# NG3ControllerBoard.net
KiCad netlist of a schematic drawn in EAGLE
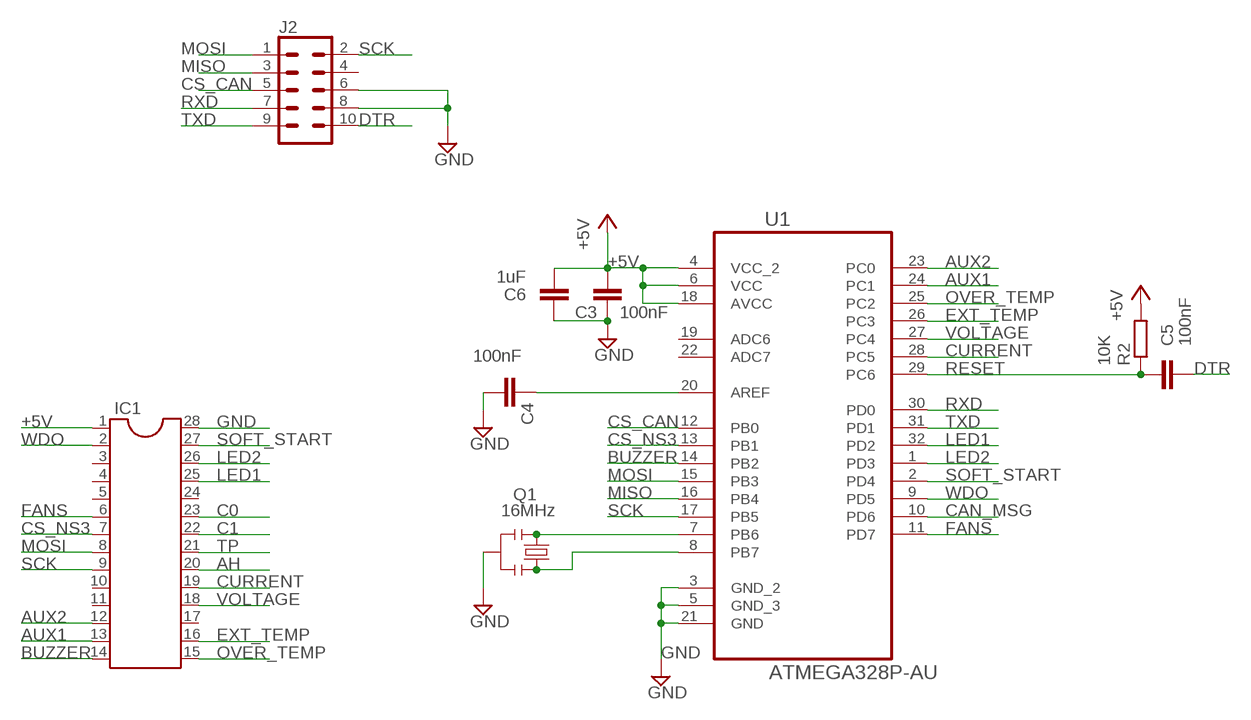
[diagram p0: schematic, sheet 1]

(export (version "E")
  (design (tool "Eeschema 10.0.6"))
  (components
    (comp (ref "C3")
      (value "100nF")
      (footprint "eagle-import:C0603")
      (libsource (lib "eagle-import") (part "C-EUC0603"))
    )
    (comp (ref "C4")
      (value "100nF")
      (footprint "eagle-import:C0603")
      (libsource (lib "eagle-import") (part "C-EUC0603"))
    )
    (comp (ref "C5")
      (value "100nF")
      (footprint "eagle-import:C0603")
      (libsource (lib "eagle-import") (part "C-EUC0603"))
    )
    (comp (ref "C6")
      (value "1uF")
      (footprint "eagle-import:C0805")
      (libsource (lib "eagle-import") (part "C-EUC0805"))
    )
    (comp (ref "IC1")
      (value "DIL28")
      (footprint "eagle-import:DIL28-6")
      (libsource (lib "eagle-import") (part "DIL28"))
    )
    (comp (ref "J2")
      (value "CONN_05X2PTH")
      (footprint "eagle-import:2X5")
      (libsource (lib "eagle-import") (part "CONN_05X2PTH"))
    )
    (comp (ref "Q1")
      (value "16MHz")
      (footprint "eagle-import:RESONATOR-SMD")
      (libsource (lib "eagle-import") (part "RESONATORSMD"))
    )
    (comp (ref "R2")
      (value "10K")
      (footprint "eagle-import:R0603")
      (libsource (lib "eagle-import") (part "R-EU_R0603"))
    )
    (comp (ref "U1")
      (value "ATMEGA328P-AU")
      (footprint "eagle-import:QFP80P900X900X120-32N")
      (libsource (lib "eagle-import") (part "ATMEGA328P-AU"))
    )
  )
  (nets
    (net (code "1") (name "+5V") (class "Default")
      (node (ref "C3") (pin "2") (pinfunction "2_2") (pintype "passive"))
      (node (ref "C6") (pin "2") (pinfunction "2_2") (pintype "passive"))
      (node (ref "IC1") (pin "1") (pinfunction "1_1") (pintype "passive"))
      (node (ref "R2") (pin "2") (pinfunction "2_2") (pintype "passive"))
      (node (ref "U1") (pin "18") (pinfunction "AVCC_18") (pintype "power_in"))
      (node (ref "U1") (pin "4") (pinfunction "VCC_2_4") (pintype "power_in"))
      (node (ref "U1") (pin "6") (pinfunction "VCC_6") (pintype "power_in"))
    )
    (net (code "2") (name "/AH") (class "Default")
      (node (ref "IC1") (pin "20") (pinfunction "20_20") (pintype "passive"))
    )
    (net (code "3") (name "/AUX1") (class "Default")
      (node (ref "IC1") (pin "13") (pinfunction "13_13") (pintype "passive"))
      (node (ref "U1") (pin "24") (pinfunction "PC1_24") (pintype "bidirectional"))
    )
    (net (code "4") (name "/AUX2") (class "Default")
      (node (ref "IC1") (pin "12") (pinfunction "12_12") (pintype "passive"))
      (node (ref "U1") (pin "23") (pinfunction "PC0_23") (pintype "bidirectional"))
    )
    (net (code "5") (name "/BUZZER") (class "Default")
      (node (ref "IC1") (pin "14") (pinfunction "14_14") (pintype "passive"))
      (node (ref "U1") (pin "14") (pinfunction "PB2_14") (pintype "bidirectional"))
    )
    (net (code "6") (name "/C0") (class "Default")
      (node (ref "IC1") (pin "23") (pinfunction "23_23") (pintype "passive"))
    )
    (net (code "7") (name "/C1") (class "Default")
      (node (ref "IC1") (pin "22") (pinfunction "22_22") (pintype "passive"))
    )
    (net (code "8") (name "/CAN_MSG") (class "Default")
      (node (ref "U1") (pin "10") (pinfunction "PD6_10") (pintype "bidirectional"))
    )
    (net (code "9") (name "/CS_CAN") (class "Default")
      (node (ref "J2") (pin "5") (pinfunction "5_5") (pintype "passive"))
      (node (ref "U1") (pin "12") (pinfunction "PB0_12") (pintype "bidirectional"))
    )
    (net (code "10") (name "/CS_NS3") (class "Default")
      (node (ref "IC1") (pin "7") (pinfunction "7_7") (pintype "passive"))
      (node (ref "U1") (pin "13") (pinfunction "PB1_13") (pintype "bidirectional"))
    )
    (net (code "11") (name "/CURRENT") (class "Default")
      (node (ref "IC1") (pin "19") (pinfunction "19_19") (pintype "passive"))
      (node (ref "U1") (pin "28") (pinfunction "PC5_28") (pintype "bidirectional"))
    )
    (net (code "12") (name "/DTR") (class "Default")
      (node (ref "C5") (pin "2") (pinfunction "2_2") (pintype "passive"))
      (node (ref "J2") (pin "10") (pinfunction "10_10") (pintype "passive"))
    )
    (net (code "13") (name "/EXT_TEMP") (class "Default")
      (node (ref "IC1") (pin "16") (pinfunction "16_16") (pintype "passive"))
      (node (ref "U1") (pin "26") (pinfunction "PC3_26") (pintype "bidirectional"))
    )
    (net (code "14") (name "/FANS") (class "Default")
      (node (ref "IC1") (pin "6") (pinfunction "6_6") (pintype "passive"))
      (node (ref "U1") (pin "11") (pinfunction "PD7_11") (pintype "bidirectional"))
    )
    (net (code "15") (name "/LED1") (class "Default")
      (node (ref "IC1") (pin "25") (pinfunction "25_25") (pintype "passive"))
      (node (ref "U1") (pin "32") (pinfunction "PD2_32") (pintype "bidirectional"))
    )
    (net (code "16") (name "/LED2") (class "Default")
      (node (ref "IC1") (pin "26") (pinfunction "26_26") (pintype "passive"))
      (node (ref "U1") (pin "1") (pinfunction "PD3_1") (pintype "bidirectional"))
    )
    (net (code "17") (name "/MISO") (class "Default")
      (node (ref "J2") (pin "3") (pinfunction "3_3") (pintype "passive"))
      (node (ref "U1") (pin "16") (pinfunction "PB4_16") (pintype "bidirectional"))
    )
    (net (code "18") (name "/MOSI") (class "Default")
      (node (ref "IC1") (pin "8") (pinfunction "8_8") (pintype "passive"))
      (node (ref "J2") (pin "1") (pinfunction "1_1") (pintype "passive"))
      (node (ref "U1") (pin "15") (pinfunction "PB3_15") (pintype "bidirectional"))
    )
    (net (code "19") (name "/OVER_TEMP") (class "Default")
      (node (ref "IC1") (pin "15") (pinfunction "15_15") (pintype "passive"))
      (node (ref "U1") (pin "25") (pinfunction "PC2_25") (pintype "bidirectional"))
    )
    (net (code "20") (name "/RESET") (class "Default")
      (node (ref "C5") (pin "1") (pinfunction "1_1") (pintype "passive"))
      (node (ref "R2") (pin "1") (pinfunction "1_1") (pintype "passive"))
      (node (ref "U1") (pin "29") (pinfunction "PC6_29") (pintype "bidirectional"))
    )
    (net (code "21") (name "/RXD") (class "Default")
      (node (ref "J2") (pin "7") (pinfunction "7_7") (pintype "passive"))
      (node (ref "U1") (pin "30") (pinfunction "PD0_30") (pintype "bidirectional"))
    )
    (net (code "22") (name "/SCK") (class "Default")
      (node (ref "IC1") (pin "9") (pinfunction "9_9") (pintype "passive"))
      (node (ref "J2") (pin "2") (pinfunction "2_2") (pintype "passive"))
      (node (ref "U1") (pin "17") (pinfunction "PB5_17") (pintype "bidirectional"))
    )
    (net (code "23") (name "/SOFT_START") (class "Default")
      (node (ref "IC1") (pin "27") (pinfunction "27_27") (pintype "passive"))
      (node (ref "U1") (pin "2") (pinfunction "PD4_2") (pintype "bidirectional"))
    )
    (net (code "24") (name "/TP") (class "Default")
      (node (ref "IC1") (pin "21") (pinfunction "21_21") (pintype "passive"))
    )
    (net (code "25") (name "/TXD") (class "Default")
      (node (ref "J2") (pin "9") (pinfunction "9_9") (pintype "passive"))
      (node (ref "U1") (pin "31") (pinfunction "PD1_31") (pintype "bidirectional"))
    )
    (net (code "26") (name "/VOLTAGE") (class "Default")
      (node (ref "IC1") (pin "18") (pinfunction "18_18") (pintype "passive"))
      (node (ref "U1") (pin "27") (pinfunction "PC4_27") (pintype "bidirectional"))
    )
    (net (code "27") (name "/WDO") (class "Default")
      (node (ref "IC1") (pin "2") (pinfunction "2_2") (pintype "passive"))
      (node (ref "U1") (pin "9") (pinfunction "PD5_9") (pintype "bidirectional"))
    )
    (net (code "28") (name "GND") (class "Default")
      (node (ref "C3") (pin "1") (pinfunction "1_1") (pintype "passive"))
      (node (ref "C4") (pin "2") (pinfunction "2_2") (pintype "passive"))
      (node (ref "C6") (pin "1") (pinfunction "1_1") (pintype "passive"))
      (node (ref "IC1") (pin "28") (pinfunction "28_28") (pintype "passive"))
      (node (ref "J2") (pin "6") (pinfunction "6_6") (pintype "passive"))
      (node (ref "J2") (pin "8") (pinfunction "8_8") (pintype "passive"))
      (node (ref "Q1") (pin "2") (pinfunction "2_2") (pintype "passive"))
      (node (ref "U1") (pin "21") (pinfunction "GND_21") (pintype "passive"))
      (node (ref "U1") (pin "3") (pinfunction "GND_2_3") (pintype "passive"))
      (node (ref "U1") (pin "5") (pinfunction "GND_3_5") (pintype "passive"))
    )
    (net (code "29") (name "Net-(U1-AREF)") (class "Default")
      (node (ref "C4") (pin "1") (pinfunction "1_1") (pintype "passive"))
      (node (ref "U1") (pin "20") (pinfunction "AREF_20") (pintype "input"))
    )
    (net (code "30") (name "Net-(U1-PB6)") (class "Default")
      (node (ref "Q1") (pin "1") (pinfunction "1_1") (pintype "passive"))
      (node (ref "U1") (pin "7") (pinfunction "PB6_7") (pintype "bidirectional"))
    )
    (net (code "31") (name "Net-(U1-PB7)") (class "Default")
      (node (ref "Q1") (pin "3") (pinfunction "3_3") (pintype "passive"))
      (node (ref "U1") (pin "8") (pinfunction "PB7_8") (pintype "bidirectional"))
    )
    (net (code "32") (name "unconnected-(IC1-Pad3)") (class "Default")
      (node (ref "IC1") (pin "3") (pinfunction "3_3") (pintype "passive"))
    )
    (net (code "33") (name "unconnected-(IC1-Pad4)") (class "Default")
      (node (ref "IC1") (pin "4") (pinfunction "4_4") (pintype "passive"))
    )
    (net (code "34") (name "unconnected-(IC1-Pad5)") (class "Default")
      (node (ref "IC1") (pin "5") (pinfunction "5_5") (pintype "passive"))
    )
    (net (code "35") (name "unconnected-(IC1-Pad10)") (class "Default")
      (node (ref "IC1") (pin "10") (pinfunction "10_10") (pintype "passive"))
    )
    (net (code "36") (name "unconnected-(IC1-Pad11)") (class "Default")
      (node (ref "IC1") (pin "11") (pinfunction "11_11") (pintype "passive"))
    )
    (net (code "37") (name "unconnected-(IC1-Pad17)") (class "Default")
      (node (ref "IC1") (pin "17") (pinfunction "17_17") (pintype "passive"))
    )
    (net (code "38") (name "unconnected-(IC1-Pad24)") (class "Default")
      (node (ref "IC1") (pin "24") (pinfunction "24_24") (pintype "passive"))
    )
    (net (code "39") (name "unconnected-(J2-Pad4)") (class "Default")
      (node (ref "J2") (pin "4") (pinfunction "4_4") (pintype "passive"))
    )
    (net (code "40") (name "unconnected-(U1-ADC6-Pad19)") (class "Default")
      (node (ref "U1") (pin "19") (pinfunction "ADC6_19") (pintype "input"))
    )
    (net (code "41") (name "unconnected-(U1-ADC7-Pad22)") (class "Default")
      (node (ref "U1") (pin "22") (pinfunction "ADC7_22") (pintype "input"))
    )
  )
)
